# Temp.net
KiCad netlist of a schematic drawn in Altium Designer
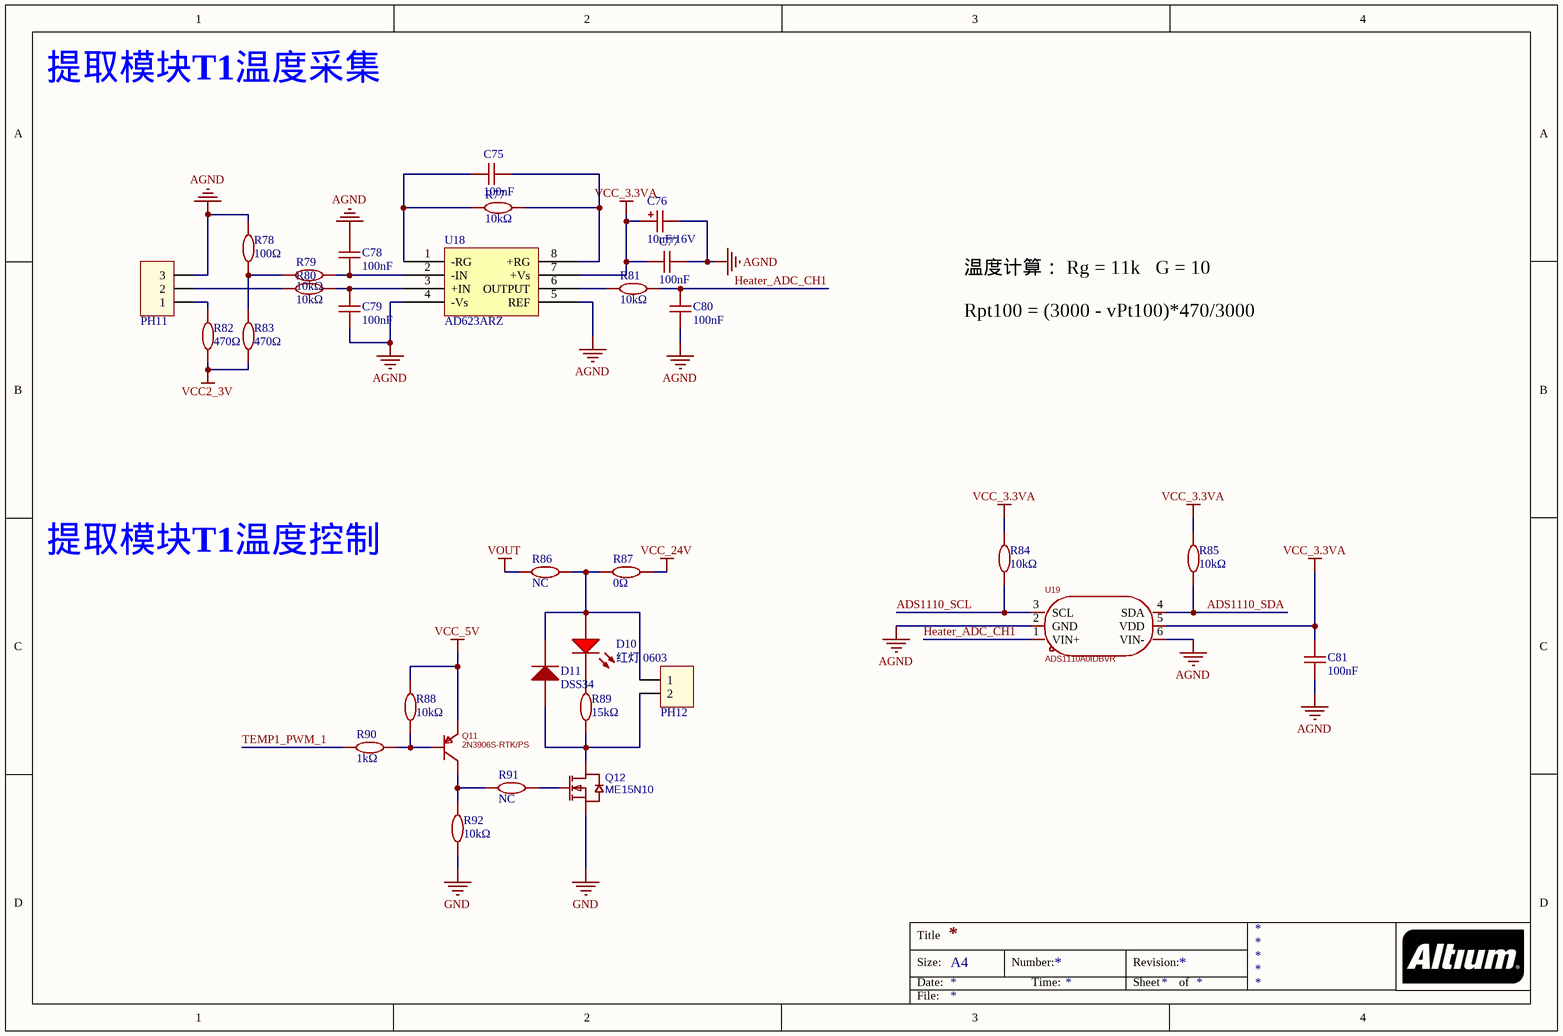
[diagram p0: Temp.SchDoc]

(export (version "E")
  (design (tool "Eeschema 10.0.6"))
  (components
    (comp (ref "C75")
      (value "100nF")
      (footprint "C0603")
      (description "贴片电容,X7R")
      (libsource (lib "XG_DW_POCT_2K10LED_3") (part "100nF/50V,C0603"))
    )
    (comp (ref "C76")
      (value "10uF/16V")
      (footprint "CASE-A_3216")
      (description "钽电容;±10%;16V")
      (libsource (lib "XG_DW_POCT_2K10LED_3") (part "10uF/16V,CASE-A_3216"))
    )
    (comp (ref "C77")
      (value "100nF")
      (footprint "C0603")
      (description "贴片电容,X7R")
      (libsource (lib "XG_DW_POCT_2K10LED_3") (part "100nF/50V,C0603"))
    )
    (comp (ref "C78")
      (value "100nF")
      (footprint "C0603")
      (description "贴片电容,X7R")
      (libsource (lib "XG_DW_POCT_2K10LED_3") (part "100nF/50V,C0603"))
    )
    (comp (ref "C79")
      (value "100nF")
      (footprint "C0603")
      (description "贴片电容,X7R")
      (libsource (lib "XG_DW_POCT_2K10LED_3") (part "100nF/50V,C0603"))
    )
    (comp (ref "C80")
      (value "100nF")
      (footprint "C0603")
      (description "贴片电容,X7R")
      (libsource (lib "XG_DW_POCT_2K10LED_3") (part "100nF/50V,C0603"))
    )
    (comp (ref "C81")
      (value "100nF")
      (footprint "C0603")
      (description "贴片电容,X7R")
      (libsource (lib "XG_DW_POCT_2K10LED_3") (part "100nF/50V,C0603"))
    )
    (comp (ref "D10")
      (value "红灯 0603")
      (footprint "LED_0603")
      (description "发光二极管")
      (libsource (lib "XG_DW_POCT_2K10LED_3") (part "红灯 0603"))
    )
    (comp (ref "D11")
      (value "DSS34")
      (footprint "SOD-123")
      (description "肖特基二极管")
      (libsource (lib "XG_DW_POCT_2K10LED_3") (part "DSS34,SOD-123"))
    )
    (comp (ref "PH11")
      (value "PH2.0-3P")
      (footprint "PH2.0-3P 弯针")
      (libsource (lib "XG_DW_POCT_2K10LED_3") (part "PH2.0-3P"))
    )
    (comp (ref "PH12")
      (value "PH2.0-2P")
      (footprint "PH2.0-2P 弯针")
      (libsource (lib "XG_DW_POCT_2K10LED_3") (part "PH2.0-2P"))
    )
    (comp (ref "Q11")
      (value "2N3906S-RTK/PS")
      (footprint "SOT-23-3_L2.9-W1.3-P1.90-LS2.4-TR")
      (fields (field (name "MANUFACTURER") "KEC"))
      (libsource (lib "XG_DW_POCT_2K10LED_3") (part "2N3906S-RTK/PS"))
    )
    (comp (ref "Q12")
      (value "ME15N10")
      (footprint "TO-252-2_L6.6-W6.1-P4.57-LS9.9-TL-CW")
      (description "场效应管(MOSFET);N沟道")
      (libsource (lib "XG_DW_POCT_2K10LED_3") (part "ME15N10"))
    )
    (comp (ref "R77")
      (value "10kΩ")
      (footprint "R0603")
      (description "电阻类型:厚膜电阻;阻值:10kΩ;精度:±1%;功率:100mW;最大工作电压:75V;温度系数:±100ppm/℃;")
      (libsource (lib "XG_DW_POCT_2K10LED_3") (part "10kΩ,R0603"))
    )
    (comp (ref "R78")
      (value "100Ω")
      (footprint "R0603")
      (description "贴片电阻")
      (libsource (lib "XG_DW_POCT_2K10LED_3") (part "100Ω,R0603"))
    )
    (comp (ref "R79")
      (value "10kΩ")
      (footprint "R0603")
      (description "电阻类型:厚膜电阻;阻值:10kΩ;精度:±1%;功率:100mW;最大工作电压:75V;温度系数:±100ppm/℃;")
      (libsource (lib "XG_DW_POCT_2K10LED_3") (part "10kΩ,R0603"))
    )
    (comp (ref "R80")
      (value "10kΩ")
      (footprint "R0603")
      (description "电阻类型:厚膜电阻;阻值:10kΩ;精度:±1%;功率:100mW;最大工作电压:75V;温度系数:±100ppm/℃;")
      (libsource (lib "XG_DW_POCT_2K10LED_3") (part "10kΩ,R0603"))
    )
    (comp (ref "R81")
      (value "10kΩ")
      (footprint "R0603")
      (description "电阻类型:厚膜电阻;阻值:10kΩ;精度:±1%;功率:100mW;最大工作电压:75V;温度系数:±100ppm/℃;")
      (libsource (lib "XG_DW_POCT_2K10LED_3") (part "10kΩ,R0603"))
    )
    (comp (ref "R82")
      (value "470Ω")
      (footprint "R0603")
      (description "贴片电阻")
      (libsource (lib "XG_DW_POCT_2K10LED_3") (part "470Ω,R0603"))
    )
    (comp (ref "R83")
      (value "470Ω")
      (footprint "R0603")
      (description "贴片电阻")
      (libsource (lib "XG_DW_POCT_2K10LED_3") (part "470Ω,R0603"))
    )
    (comp (ref "R84")
      (value "10kΩ")
      (footprint "R0603")
      (description "电阻类型:厚膜电阻;阻值:10kΩ;精度:±1%;功率:100mW;最大工作电压:75V;温度系数:±100ppm/℃;")
      (libsource (lib "XG_DW_POCT_2K10LED_3") (part "10kΩ,R0603"))
    )
    (comp (ref "R85")
      (value "10kΩ")
      (footprint "R0603")
      (description "电阻类型:厚膜电阻;阻值:10kΩ;精度:±1%;功率:100mW;最大工作电压:75V;温度系数:±100ppm/℃;")
      (libsource (lib "XG_DW_POCT_2K10LED_3") (part "10kΩ,R0603"))
    )
    (comp (ref "R86")
      (value "NC")
      (footprint "R1206")
      (description "贴片电阻")
      (libsource (lib "XG_DW_POCT_2K10LED_3") (part "NC,R1206"))
    )
    (comp (ref "R87")
      (value "0Ω")
      (footprint "R1206")
      (description "贴片电阻")
      (libsource (lib "XG_DW_POCT_2K10LED_3") (part "0Ω,R1206"))
    )
    (comp (ref "R88")
      (value "10kΩ")
      (footprint "R0603")
      (description "电阻类型:厚膜电阻;阻值:10kΩ;精度:±1%;功率:100mW;最大工作电压:75V;温度系数:±100ppm/℃;")
      (libsource (lib "XG_DW_POCT_2K10LED_3") (part "10kΩ,R0603"))
    )
    (comp (ref "R89")
      (value "15kΩ")
      (footprint "R0603")
      (description "贴片电阻")
      (libsource (lib "XG_DW_POCT_2K10LED_3") (part "15kΩ,R0603"))
    )
    (comp (ref "R90")
      (value "1kΩ")
      (footprint "R0603")
      (description "电阻类型:厚膜电阻;阻值:1kΩ;精度:±1%;功率:125mW;最大工作电压:150V;温度系数:±100ppm/℃;")
      (libsource (lib "XG_DW_POCT_2K10LED_3") (part "1kΩ,R0603"))
    )
    (comp (ref "R91")
      (value "NC")
      (footprint "R0603")
      (libsource (lib "XG_DW_POCT_2K10LED_3") (part "NC,R0603"))
    )
    (comp (ref "R92")
      (value "10kΩ")
      (footprint "R0603")
      (description "电阻类型:厚膜电阻;阻值:10kΩ;精度:±1%;功率:100mW;最大工作电压:75V;温度系数:±100ppm/℃;")
      (libsource (lib "XG_DW_POCT_2K10LED_3") (part "10kΩ,R0603"))
    )
    (comp (ref "U18")
      (value "AD623ARZ")
      (footprint "SOP-8_150mil")
      (libsource (lib "XG_DW_POCT_2K10LED_3") (part "AD623ARZ"))
    )
    (comp (ref "U19")
      (value "ADS1110A0IDBVR")
      (footprint "SOT-23-6_L2.9-W1.6-P0.95-LS2.8-BR")
      (fields (field (name "MANUFACTURER") "TI(德州仪器)"))
      (libsource (lib "XG_DW_POCT_2K10LED_3") (part "ADS1110A0IDBVR"))
    )
  )
  (nets
    (net (code "1") (name "/ADS1110_SCL") (class "Default")
      (node (ref "R84") (pin "2") (pinfunction "2_2") (pintype "passive"))
      (node (ref "U19") (pin "3") (pinfunction "SCL_3") (pintype "passive"))
    )
    (net (code "2") (name "/ADS1110_SDA") (class "Default")
      (node (ref "R85") (pin "2") (pinfunction "2_2") (pintype "passive"))
      (node (ref "U19") (pin "4") (pinfunction "SDA_4") (pintype "passive"))
    )
    (net (code "3") (name "/Heater_ADC_CH1") (class "Default")
      (node (ref "C80") (pin "2") (pinfunction "2_2") (pintype "passive"))
      (node (ref "R81") (pin "2") (pinfunction "2_2") (pintype "passive"))
      (node (ref "U19") (pin "1") (pinfunction "VIN+_1") (pintype "passive"))
    )
    (net (code "4") (name "/TEMP1_PWM_1") (class "Default")
      (node (ref "R90") (pin "1") (pinfunction "1_1") (pintype "passive"))
    )
    (net (code "5") (name "AGND") (class "Default")
      (node (ref "C76") (pin "2") (pinfunction "2_2") (pintype "passive"))
      (node (ref "C77") (pin "2") (pinfunction "2_2") (pintype "passive"))
      (node (ref "C78") (pin "2") (pinfunction "2_2") (pintype "passive"))
      (node (ref "C79") (pin "1") (pinfunction "1_1") (pintype "passive"))
      (node (ref "C80") (pin "1") (pinfunction "1_1") (pintype "passive"))
      (node (ref "C81") (pin "1") (pinfunction "1_1") (pintype "passive"))
      (node (ref "PH11") (pin "3") (pinfunction "3_3") (pintype "passive"))
      (node (ref "R78") (pin "2") (pinfunction "2_2") (pintype "passive"))
      (node (ref "U18") (pin "4") (pinfunction "-Vs_4") (pintype "passive"))
      (node (ref "U18") (pin "5") (pinfunction "REF_5") (pintype "passive"))
      (node (ref "U19") (pin "2") (pinfunction "GND_2") (pintype "passive"))
      (node (ref "U19") (pin "6") (pinfunction "VIN-_6") (pintype "passive"))
    )
    (net (code "6") (name "GND") (class "Default")
      (node (ref "Q12") (pin "3") (pinfunction "S_3") (pintype "passive"))
      (node (ref "R92") (pin "2") (pinfunction "2_2") (pintype "passive"))
    )
    (net (code "7") (name "Net-(D10-PadK)") (class "Default")
      (node (ref "D10") (pin "K") (pinfunction "K_K") (pintype "passive"))
      (node (ref "R89") (pin "2") (pinfunction "2_2") (pintype "passive"))
    )
    (net (code "8") (name "Net-(D11-A)") (class "Default")
      (node (ref "D11") (pin "1") (pinfunction "A_1") (pintype "passive"))
      (node (ref "PH12") (pin "2") (pinfunction "2_2") (pintype "passive"))
      (node (ref "Q12") (pin "2") (pinfunction "D_2") (pintype "passive"))
      (node (ref "R89") (pin "1") (pinfunction "1_1") (pintype "passive"))
    )
    (net (code "9") (name "Net-(D11-K)") (class "Default")
      (node (ref "D10") (pin "A") (pinfunction "A_A") (pintype "passive"))
      (node (ref "D11") (pin "2") (pinfunction "K_2") (pintype "passive"))
      (node (ref "PH12") (pin "1") (pinfunction "1_1") (pintype "passive"))
      (node (ref "R86") (pin "2") (pinfunction "2_2") (pintype "passive"))
      (node (ref "R87") (pin "1") (pinfunction "1_1") (pintype "passive"))
    )
    (net (code "10") (name "Net-(PH11-Pad1)") (class "Default")
      (node (ref "PH11") (pin "1") (pinfunction "1_1") (pintype "passive"))
      (node (ref "R82") (pin "2") (pinfunction "2_2") (pintype "passive"))
    )
    (net (code "11") (name "Net-(PH11-Pad2)") (class "Default")
      (node (ref "PH11") (pin "2") (pinfunction "2_2") (pintype "passive"))
      (node (ref "R80") (pin "2") (pinfunction "2_2") (pintype "passive"))
    )
    (net (code "12") (name "Net-(Q11-B)") (class "Default")
      (node (ref "Q11") (pin "2") (pinfunction "B_2") (pintype "passive"))
      (node (ref "R88") (pin "2") (pinfunction "2_2") (pintype "passive"))
      (node (ref "R90") (pin "2") (pinfunction "2_2") (pintype "passive"))
    )
    (net (code "13") (name "Net-(Q11-C)") (class "Default")
      (node (ref "Q11") (pin "3") (pinfunction "C_3") (pintype "passive"))
      (node (ref "R91") (pin "1") (pinfunction "1_1") (pintype "passive"))
      (node (ref "R92") (pin "1") (pinfunction "1_1") (pintype "passive"))
    )
    (net (code "14") (name "Net-(Q12-G)") (class "Default")
      (node (ref "Q12") (pin "1") (pinfunction "G_1") (pintype "passive"))
      (node (ref "R91") (pin "2") (pinfunction "2_2") (pintype "passive"))
    )
    (net (code "15") (name "Net-(R78-Pad1)") (class "Default")
      (node (ref "R78") (pin "1") (pinfunction "1_1") (pintype "passive"))
      (node (ref "R79") (pin "2") (pinfunction "2_2") (pintype "passive"))
      (node (ref "R83") (pin "2") (pinfunction "2_2") (pintype "passive"))
    )
    (net (code "16") (name "Net-(U18-+IN)") (class "Default")
      (node (ref "C79") (pin "2") (pinfunction "2_2") (pintype "passive"))
      (node (ref "R80") (pin "1") (pinfunction "1_1") (pintype "passive"))
      (node (ref "U18") (pin "3") (pinfunction "+IN_3") (pintype "passive"))
    )
    (net (code "17") (name "Net-(U18-+RG)") (class "Default")
      (node (ref "C75") (pin "2") (pinfunction "2_2") (pintype "passive"))
      (node (ref "R77") (pin "2") (pinfunction "2_2") (pintype "passive"))
      (node (ref "U18") (pin "8") (pinfunction "+RG_8") (pintype "passive"))
    )
    (net (code "18") (name "Net-(U18--IN)") (class "Default")
      (node (ref "C78") (pin "1") (pinfunction "1_1") (pintype "passive"))
      (node (ref "R79") (pin "1") (pinfunction "1_1") (pintype "passive"))
      (node (ref "U18") (pin "2") (pinfunction "-IN_2") (pintype "passive"))
    )
    (net (code "19") (name "Net-(U18--RG)") (class "Default")
      (node (ref "C75") (pin "1") (pinfunction "1_1") (pintype "passive"))
      (node (ref "R77") (pin "1") (pinfunction "1_1") (pintype "passive"))
      (node (ref "U18") (pin "1") (pinfunction "-RG_1") (pintype "passive"))
    )
    (net (code "20") (name "Net-(U18-OUTPUT)") (class "Default")
      (node (ref "R81") (pin "1") (pinfunction "1_1") (pintype "passive"))
      (node (ref "U18") (pin "6") (pinfunction "OUTPUT_6") (pintype "passive"))
    )
    (net (code "21") (name "VCC2_3V") (class "Default")
      (node (ref "R82") (pin "1") (pinfunction "1_1") (pintype "passive"))
      (node (ref "R83") (pin "1") (pinfunction "1_1") (pintype "passive"))
    )
    (net (code "22") (name "VCC_3.3VA") (class "Default")
      (node (ref "C76") (pin "1") (pinfunction "1_1") (pintype "passive"))
      (node (ref "C77") (pin "1") (pinfunction "1_1") (pintype "passive"))
      (node (ref "C81") (pin "2") (pinfunction "2_2") (pintype "passive"))
      (node (ref "R84") (pin "1") (pinfunction "1_1") (pintype "passive"))
      (node (ref "R85") (pin "1") (pinfunction "1_1") (pintype "passive"))
      (node (ref "U18") (pin "7") (pinfunction "+Vs_7") (pintype "passive"))
      (node (ref "U19") (pin "5") (pinfunction "VDD_5") (pintype "passive"))
    )
    (net (code "23") (name "VCC_5V") (class "Default")
      (node (ref "Q11") (pin "1") (pinfunction "E_1") (pintype "passive"))
      (node (ref "R88") (pin "1") (pinfunction "1_1") (pintype "passive"))
    )
    (net (code "24") (name "VCC_24V") (class "Default")
      (node (ref "R87") (pin "2") (pinfunction "2_2") (pintype "passive"))
    )
    (net (code "25") (name "VOUT") (class "Default")
      (node (ref "R86") (pin "1") (pinfunction "1_1") (pintype "passive"))
    )
  )
)
